# Car_Engine_Room.net
KiCad netlist of a schematic drawn in EAGLE
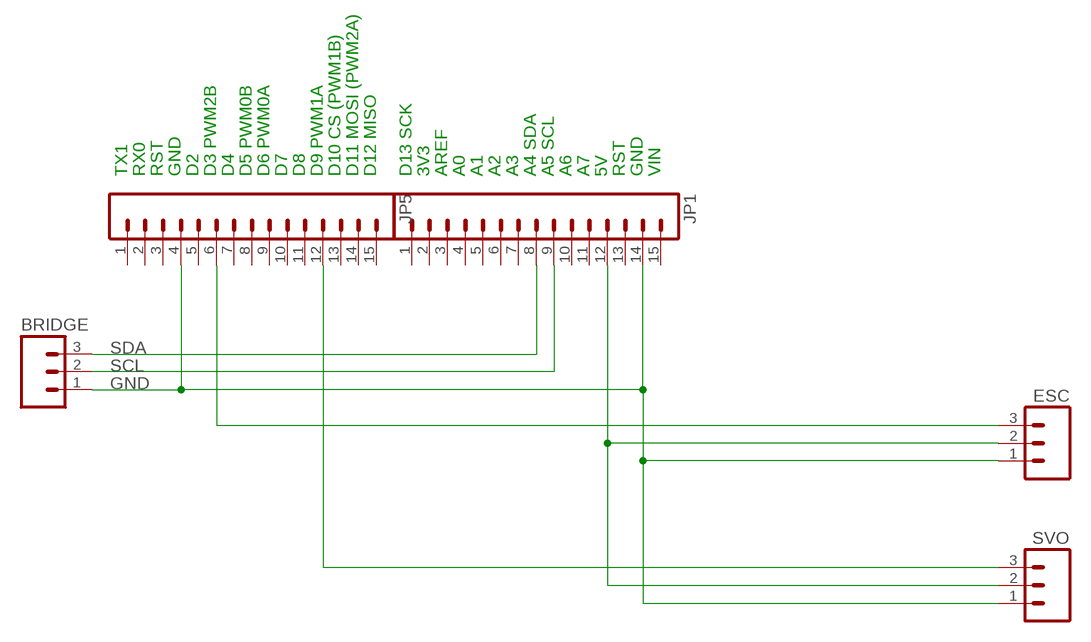
[diagram p0: schematic, sheet 1]

(export (version "E")
  (design (tool "Eeschema 10.0.6"))
  (components
    (comp (ref "BRIDGE")
      (value "M03PTH")
      (footprint "eagle-import:1X03")
      (libsource (lib "eagle-import") (part "M03PTH"))
    )
    (comp (ref "ESC")
      (value "M03PTH")
      (footprint "eagle-import:1X03")
      (libsource (lib "eagle-import") (part "M03PTH"))
    )
    (comp (ref "JP1")
      (value "M15")
      (footprint "eagle-import:1X15")
      (libsource (lib "eagle-import") (part "M15"))
    )
    (comp (ref "JP5")
      (value "M15")
      (footprint "eagle-import:1X15")
      (libsource (lib "eagle-import") (part "M15"))
    )
    (comp (ref "SVO")
      (value "M03PTH")
      (footprint "eagle-import:1X03")
      (libsource (lib "eagle-import") (part "M03PTH"))
    )
  )
  (nets
    (net (code "1") (name "/GND") (class "Default")
      (node (ref "BRIDGE") (pin "1") (pinfunction "1_1") (pintype "passive"))
      (node (ref "ESC") (pin "1") (pinfunction "1_1") (pintype "passive"))
      (node (ref "JP1") (pin "14") (pinfunction "14_14") (pintype "passive"))
      (node (ref "JP5") (pin "4") (pinfunction "4_4") (pintype "passive"))
      (node (ref "SVO") (pin "1") (pinfunction "1_1") (pintype "passive"))
    )
    (net (code "2") (name "/SCL") (class "Default")
      (node (ref "BRIDGE") (pin "2") (pinfunction "2_2") (pintype "passive"))
      (node (ref "JP1") (pin "9") (pinfunction "9_9") (pintype "passive"))
    )
    (net (code "3") (name "/SDA") (class "Default")
      (node (ref "BRIDGE") (pin "3") (pinfunction "3_3") (pintype "passive"))
      (node (ref "JP1") (pin "8") (pinfunction "8_8") (pintype "passive"))
    )
    (net (code "4") (name "Net-(ESC-Pad2)") (class "Default")
      (node (ref "ESC") (pin "2") (pinfunction "2_2") (pintype "passive"))
      (node (ref "JP1") (pin "12") (pinfunction "12_12") (pintype "passive"))
      (node (ref "SVO") (pin "2") (pinfunction "2_2") (pintype "passive"))
    )
    (net (code "5") (name "Net-(ESC-Pad3)") (class "Default")
      (node (ref "ESC") (pin "3") (pinfunction "3_3") (pintype "passive"))
      (node (ref "JP5") (pin "6") (pinfunction "6_6") (pintype "passive"))
    )
    (net (code "6") (name "Net-(JP5-Pad12)") (class "Default")
      (node (ref "JP5") (pin "12") (pinfunction "12_12") (pintype "passive"))
      (node (ref "SVO") (pin "3") (pinfunction "3_3") (pintype "passive"))
    )
    (net (code "7") (name "unconnected-(JP1-Pad1)") (class "Default")
      (node (ref "JP1") (pin "1") (pinfunction "1_1") (pintype "passive"))
    )
    (net (code "8") (name "unconnected-(JP1-Pad2)") (class "Default")
      (node (ref "JP1") (pin "2") (pinfunction "2_2") (pintype "passive"))
    )
    (net (code "9") (name "unconnected-(JP1-Pad3)") (class "Default")
      (node (ref "JP1") (pin "3") (pinfunction "3_3") (pintype "passive"))
    )
    (net (code "10") (name "unconnected-(JP1-Pad4)") (class "Default")
      (node (ref "JP1") (pin "4") (pinfunction "4_4") (pintype "passive"))
    )
    (net (code "11") (name "unconnected-(JP1-Pad5)") (class "Default")
      (node (ref "JP1") (pin "5") (pinfunction "5_5") (pintype "passive"))
    )
    (net (code "12") (name "unconnected-(JP1-Pad6)") (class "Default")
      (node (ref "JP1") (pin "6") (pinfunction "6_6") (pintype "passive"))
    )
    (net (code "13") (name "unconnected-(JP1-Pad7)") (class "Default")
      (node (ref "JP1") (pin "7") (pinfunction "7_7") (pintype "passive"))
    )
    (net (code "14") (name "unconnected-(JP1-Pad10)") (class "Default")
      (node (ref "JP1") (pin "10") (pinfunction "10_10") (pintype "passive"))
    )
    (net (code "15") (name "unconnected-(JP1-Pad11)") (class "Default")
      (node (ref "JP1") (pin "11") (pinfunction "11_11") (pintype "passive"))
    )
    (net (code "16") (name "unconnected-(JP1-Pad13)") (class "Default")
      (node (ref "JP1") (pin "13") (pinfunction "13_13") (pintype "passive"))
    )
    (net (code "17") (name "unconnected-(JP1-Pad15)") (class "Default")
      (node (ref "JP1") (pin "15") (pinfunction "15_15") (pintype "passive"))
    )
    (net (code "18") (name "unconnected-(JP5-Pad1)") (class "Default")
      (node (ref "JP5") (pin "1") (pinfunction "1_1") (pintype "passive"))
    )
    (net (code "19") (name "unconnected-(JP5-Pad2)") (class "Default")
      (node (ref "JP5") (pin "2") (pinfunction "2_2") (pintype "passive"))
    )
    (net (code "20") (name "unconnected-(JP5-Pad3)") (class "Default")
      (node (ref "JP5") (pin "3") (pinfunction "3_3") (pintype "passive"))
    )
    (net (code "21") (name "unconnected-(JP5-Pad5)") (class "Default")
      (node (ref "JP5") (pin "5") (pinfunction "5_5") (pintype "passive"))
    )
    (net (code "22") (name "unconnected-(JP5-Pad7)") (class "Default")
      (node (ref "JP5") (pin "7") (pinfunction "7_7") (pintype "passive"))
    )
    (net (code "23") (name "unconnected-(JP5-Pad8)") (class "Default")
      (node (ref "JP5") (pin "8") (pinfunction "8_8") (pintype "passive"))
    )
    (net (code "24") (name "unconnected-(JP5-Pad9)") (class "Default")
      (node (ref "JP5") (pin "9") (pinfunction "9_9") (pintype "passive"))
    )
    (net (code "25") (name "unconnected-(JP5-Pad10)") (class "Default")
      (node (ref "JP5") (pin "10") (pinfunction "10_10") (pintype "passive"))
    )
    (net (code "26") (name "unconnected-(JP5-Pad11)") (class "Default")
      (node (ref "JP5") (pin "11") (pinfunction "11_11") (pintype "passive"))
    )
    (net (code "27") (name "unconnected-(JP5-Pad13)") (class "Default")
      (node (ref "JP5") (pin "13") (pinfunction "13_13") (pintype "passive"))
    )
    (net (code "28") (name "unconnected-(JP5-Pad14)") (class "Default")
      (node (ref "JP5") (pin "14") (pinfunction "14_14") (pintype "passive"))
    )
    (net (code "29") (name "unconnected-(JP5-Pad15)") (class "Default")
      (node (ref "JP5") (pin "15") (pinfunction "15_15") (pintype "passive"))
    )
  )
)
